# ISO_CAN_Module.net
KiCad netlist of a schematic drawn in EAGLE
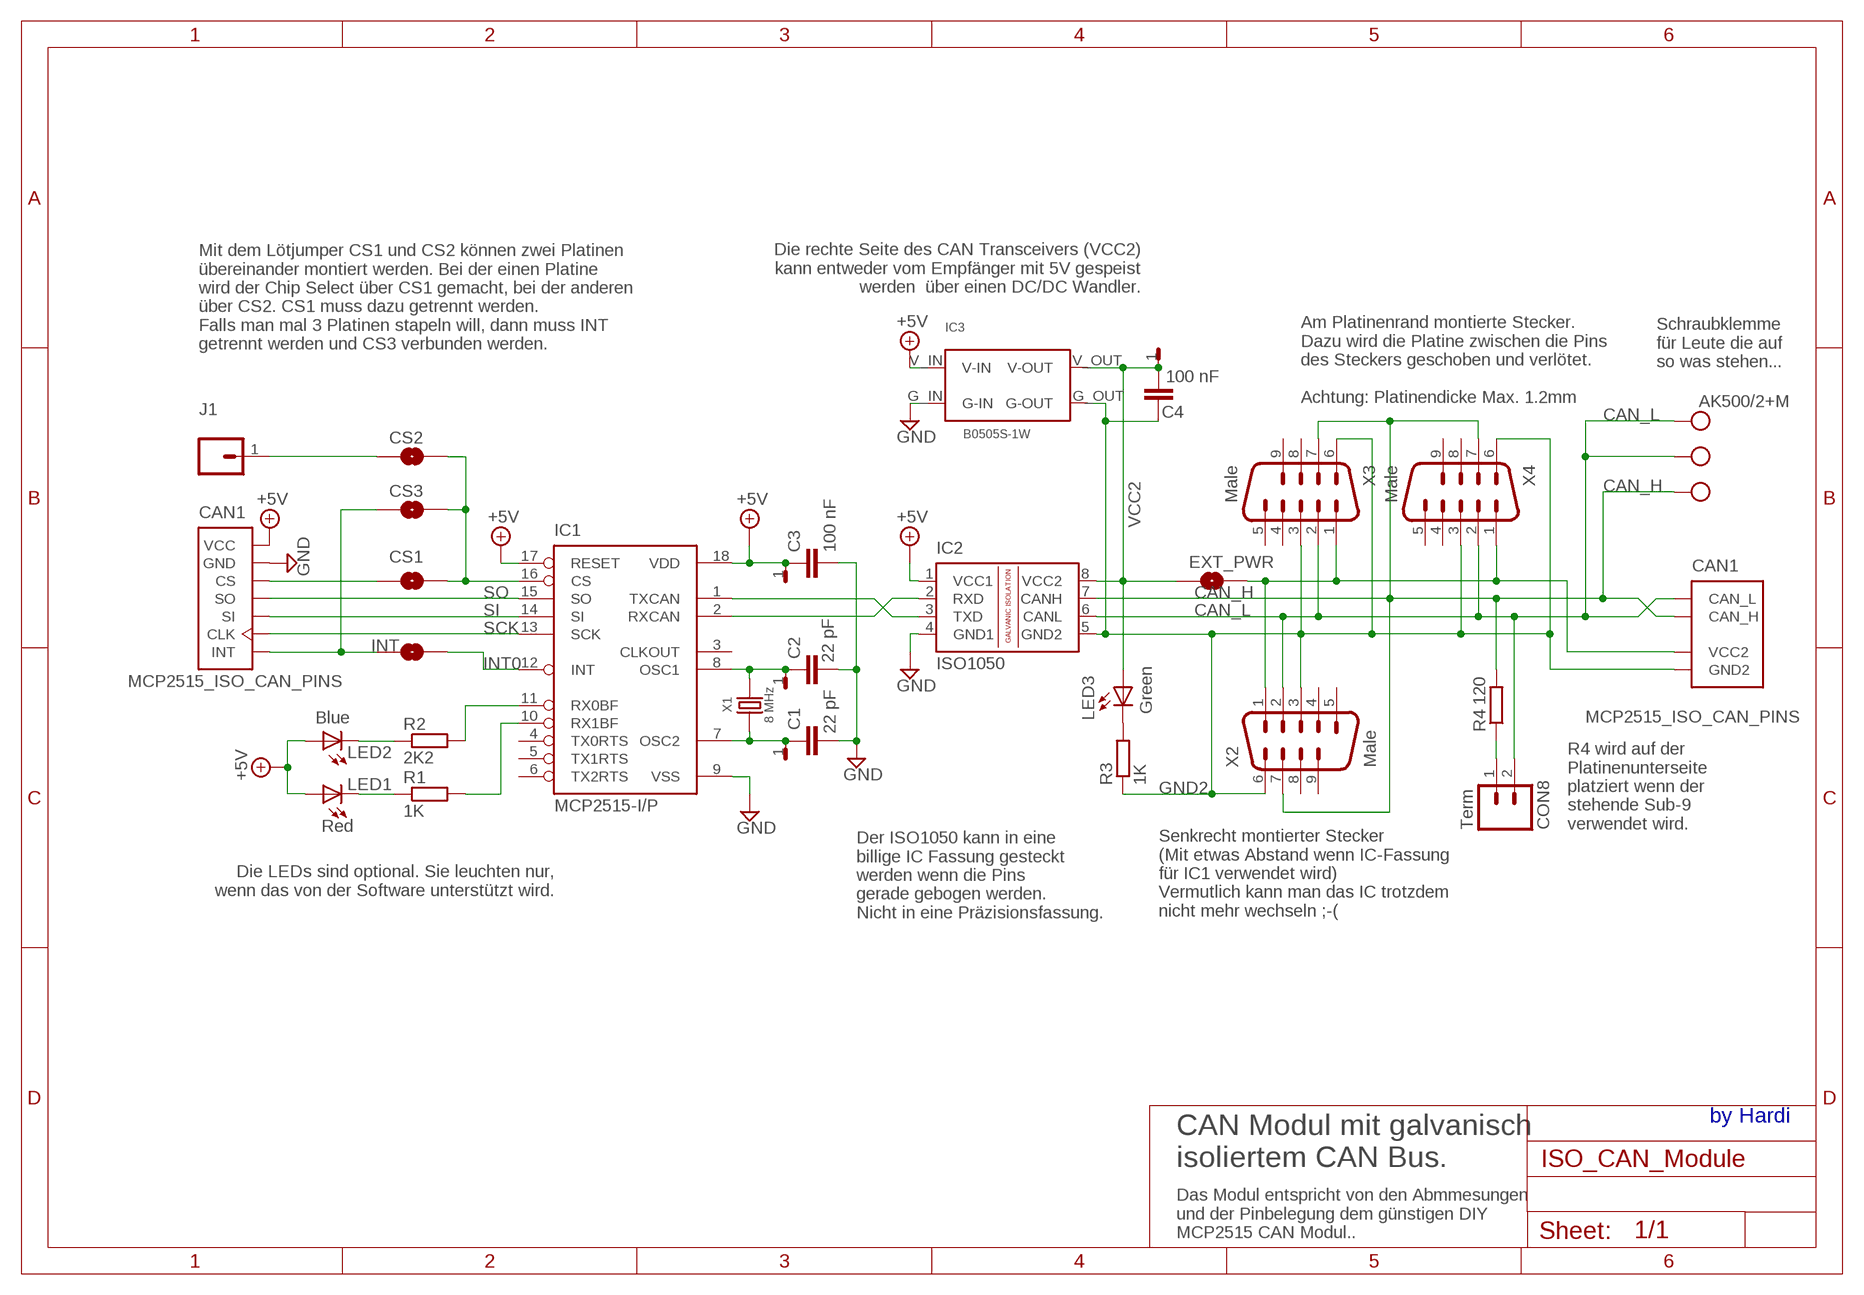
[diagram p0: schematic, sheet 1]

(export (version "E")
  (design (tool "Eeschema 10.0.6"))
  (components
    (comp (ref "C1")
      (value "22 pF")
      (footprint "eagle-import:C2.5-2")
      (libsource (lib "eagle-import") (part "C2.5/2"))
    )
    (comp (ref "C2")
      (value "22 pF")
      (footprint "eagle-import:C2.5-2")
      (libsource (lib "eagle-import") (part "C2.5/2"))
    )
    (comp (ref "C3")
      (value "100 nF")
      (footprint "eagle-import:C2.5-2")
      (libsource (lib "eagle-import") (part "C2.5/2"))
    )
    (comp (ref "C4")
      (value "100 nF")
      (footprint "eagle-import:C2.5-2")
      (libsource (lib "eagle-import") (part "C2.5/2"))
    )
    (comp (ref "CAN1")
      (value "MCP2515_ISO_CAN_PINS")
      (footprint "eagle-import:MCP2515_ISO_CAN")
      (libsource (lib "eagle-import") (part "MCP2515_ISO_CAN_PINS"))
    )
    (comp (ref "CON8")
      (value "Term")
      (footprint "eagle-import:1X02")
      (libsource (lib "eagle-import") (part "M02PTH"))
    )
    (comp (ref "CS1")
      (value "SOLDERJUMPERTRACE")
      (footprint "eagle-import:SJ_2S-TRACE")
      (libsource (lib "eagle-import") (part "SOLDERJUMPERTRACE"))
    )
    (comp (ref "CS2")
      (value "SOLDERJUMPERNO")
      (footprint "eagle-import:SJ_2S-NO")
      (libsource (lib "eagle-import") (part "SOLDERJUMPERNO"))
    )
    (comp (ref "CS3")
      (value "SOLDERJUMPERNO")
      (footprint "eagle-import:SJ_2S-NO")
      (libsource (lib "eagle-import") (part "SOLDERJUMPERNO"))
    )
    (comp (ref "EXT_PWR")
      (value "SOLDERJUMPERNO")
      (footprint "eagle-import:SJ_2S-NO")
      (libsource (lib "eagle-import") (part "SOLDERJUMPERNO"))
    )
    (comp (ref "IC1")
      (value "MCP2515-I/P")
      (footprint "eagle-import:DIL18")
      (libsource (lib "eagle-import") (part "MCP2515-I/P"))
    )
    (comp (ref "IC2")
      (value "ISO1050")
      (footprint "eagle-import:DIL08")
      (libsource (lib "eagle-import") (part "ISO1050"))
    )
    (comp (ref "IC3")
      (value "B0505S-1W")
      (footprint "eagle-import:DCDC-TEA_NME")
      (libsource (lib "eagle-import") (part "DCDC"))
    )
    (comp (ref "INT")
      (value "SOLDERJUMPERTRACE")
      (footprint "eagle-import:SJ_2S-TRACE")
      (libsource (lib "eagle-import") (part "SOLDERJUMPERTRACE"))
    )
    (comp (ref "J1")
      (value "M01")
      (footprint "eagle-import:1X01")
      (libsource (lib "eagle-import") (part "M01"))
    )
    (comp (ref "J2")
      (value "M01S")
      (footprint "eagle-import:1X01S")
      (libsource (lib "eagle-import") (part "M01S"))
    )
    (comp (ref "J3")
      (value "M01S")
      (footprint "eagle-import:1X01S")
      (libsource (lib "eagle-import") (part "M01S"))
    )
    (comp (ref "J4")
      (value "M01S")
      (footprint "eagle-import:1X01S")
      (libsource (lib "eagle-import") (part "M01S"))
    )
    (comp (ref "J5")
      (value "M01S")
      (footprint "eagle-import:1X01S")
      (libsource (lib "eagle-import") (part "M01S"))
    )
    (comp (ref "LED1")
      (value "Red")
      (footprint "eagle-import:CHIPLED_0805")
      (libsource (lib "eagle-import") (part "LEDCHIPLED_0805"))
    )
    (comp (ref "LED2")
      (value "Blue")
      (footprint "eagle-import:CHIPLED_0805")
      (libsource (lib "eagle-import") (part "LEDCHIPLED_0805"))
    )
    (comp (ref "LED3")
      (value "Green")
      (footprint "eagle-import:CHIPLED_0805")
      (libsource (lib "eagle-import") (part "LEDCHIPLED_0805"))
    )
    (comp (ref "R1")
      (value "1K")
      (footprint "eagle-import:M0805")
      (libsource (lib "eagle-import") (part "R-EU_M0805"))
    )
    (comp (ref "R2")
      (value "2K2")
      (footprint "eagle-import:M0805")
      (libsource (lib "eagle-import") (part "R-EU_M0805"))
    )
    (comp (ref "R3")
      (value "1K")
      (footprint "eagle-import:M0805")
      (libsource (lib "eagle-import") (part "R-EU_M0805"))
    )
    (comp (ref "R4")
      (value "120")
      (footprint "eagle-import:0204_7")
      (libsource (lib "eagle-import") (part "R-EU_0204/7"))
    )
    (comp (ref "X1")
      (value "8 MHz")
      (footprint "eagle-import:HC49U-V")
      (libsource (lib "eagle-import") (part "CRYSTAL-HC49U-V"))
    )
    (comp (ref "X2")
      (value "Male")
      (footprint "eagle-import:M09VB")
      (libsource (lib "eagle-import") (part "M09VB"))
    )
    (comp (ref "X3")
      (value "Male")
      (footprint "eagle-import:M09D")
      (libsource (lib "eagle-import") (part "M09D"))
    )
    (comp (ref "X4")
      (value "Male")
      (footprint "eagle-import:M09D")
      (libsource (lib "eagle-import") (part "M09D"))
    )
    (comp (ref "X5")
      (value "AK500/2+M")
      (footprint "eagle-import:AK500_2+M")
      (libsource (lib "eagle-import") (part "AK500/2+M"))
    )
  )
  (nets
    (net (code "1") (name "+5V") (class "Default")
      (node (ref "C3") (pin "1") (pinfunction "1_1") (pintype "passive"))
      (node (ref "CAN1") (pin "1") (pinfunction "VCC_1") (pintype "power_in"))
      (node (ref "IC1") (pin "17") (pinfunction "RESET_17") (pintype "input"))
      (node (ref "IC1") (pin "18") (pinfunction "VDD_18") (pintype "power_in"))
      (node (ref "IC2") (pin "1") (pinfunction "VCC1_1") (pintype "input"))
      (node (ref "IC3") (pin "V_IN") (pinfunction "V-IN_V_IN") (pintype "bidirectional"))
      (node (ref "J4") (pin "1") (pinfunction "1_1") (pintype "passive"))
      (node (ref "LED1") (pin "A") (pinfunction "A_A") (pintype "passive"))
      (node (ref "LED2") (pin "A") (pinfunction "A_A") (pintype "passive"))
    )
    (net (code "2") (name "/CAN_H") (class "Default")
      (node (ref "CAN1") (pin "9") (pinfunction "CAN_H_9") (pintype "bidirectional"))
      (node (ref "IC2") (pin "7") (pinfunction "CANH_7") (pintype "input"))
      (node (ref "R4") (pin "2") (pinfunction "2_2") (pintype "passive"))
      (node (ref "X2") (pin "7") (pinfunction "7_7") (pintype "passive"))
      (node (ref "X3") (pin "7") (pinfunction "7_7") (pintype "passive"))
      (node (ref "X4") (pin "7") (pinfunction "7_7") (pintype "passive"))
      (node (ref "X5") (pin "2") (pinfunction "KL_2") (pintype "passive"))
    )
    (net (code "3") (name "/CAN_L") (class "Default")
      (node (ref "CAN1") (pin "8") (pinfunction "CAN_L_8") (pintype "bidirectional"))
      (node (ref "CON8") (pin "2") (pinfunction "2_2") (pintype "passive"))
      (node (ref "IC2") (pin "6") (pinfunction "CANL_6") (pintype "input"))
      (node (ref "X2") (pin "2") (pinfunction "2_2") (pintype "passive"))
      (node (ref "X3") (pin "2") (pinfunction "2_2") (pintype "passive"))
      (node (ref "X4") (pin "2") (pinfunction "2_2") (pintype "passive"))
      (node (ref "X5") (pin "1") (pinfunction "KL_1") (pintype "passive"))
      (node (ref "X5") (pin "M") (pinfunction "KL_M") (pintype "passive"))
    )
    (net (code "4") (name "/GND2") (class "Default")
      (node (ref "C4") (pin "1") (pinfunction "1_1") (pintype "passive"))
      (node (ref "CAN1") (pin "11") (pinfunction "GND2_11") (pintype "power_in"))
      (node (ref "IC2") (pin "5") (pinfunction "GND2_5") (pintype "input"))
      (node (ref "IC3") (pin "G_OUT") (pinfunction "G-OUT_G_OUT") (pintype "bidirectional"))
      (node (ref "R3") (pin "1") (pinfunction "1_1") (pintype "passive"))
      (node (ref "X2") (pin "3") (pinfunction "3_3") (pintype "passive"))
      (node (ref "X2") (pin "6") (pinfunction "6_6") (pintype "passive"))
      (node (ref "X3") (pin "3") (pinfunction "3_3") (pintype "passive"))
      (node (ref "X3") (pin "6") (pinfunction "6_6") (pintype "passive"))
      (node (ref "X4") (pin "3") (pinfunction "3_3") (pintype "passive"))
      (node (ref "X4") (pin "6") (pinfunction "6_6") (pintype "passive"))
    )
    (net (code "5") (name "/INT0") (class "Default")
      (node (ref "IC1") (pin "12") (pinfunction "INT_12") (pintype "output"))
      (node (ref "INT") (pin "2") (pinfunction "2_2") (pintype "passive"))
    )
    (net (code "6") (name "/SCK") (class "Default")
      (node (ref "CAN1") (pin "6") (pinfunction "CLK_6") (pintype "input"))
      (node (ref "IC1") (pin "13") (pinfunction "SCK_13") (pintype "input"))
    )
    (net (code "7") (name "/SI") (class "Default")
      (node (ref "CAN1") (pin "5") (pinfunction "SI_5") (pintype "input"))
      (node (ref "IC1") (pin "14") (pinfunction "SI_14") (pintype "input"))
    )
    (net (code "8") (name "/SO") (class "Default")
      (node (ref "CAN1") (pin "4") (pinfunction "SO_4") (pintype "output"))
      (node (ref "IC1") (pin "15") (pinfunction "SO_15") (pintype "output"))
    )
    (net (code "9") (name "/VCC2") (class "Default")
      (node (ref "C4") (pin "2") (pinfunction "2_2") (pintype "passive"))
      (node (ref "EXT_PWR") (pin "1") (pinfunction "1_1") (pintype "passive"))
      (node (ref "IC2") (pin "8") (pinfunction "VCC2_8") (pintype "input"))
      (node (ref "IC3") (pin "V_OUT") (pinfunction "V-OUT_V_OUT") (pintype "bidirectional"))
      (node (ref "J5") (pin "1") (pinfunction "1_1") (pintype "passive"))
      (node (ref "LED3") (pin "A") (pinfunction "A_A") (pintype "passive"))
    )
    (net (code "10") (name "GND") (class "Default")
      (node (ref "C1") (pin "2") (pinfunction "2_2") (pintype "passive"))
      (node (ref "C2") (pin "2") (pinfunction "2_2") (pintype "passive"))
      (node (ref "C3") (pin "2") (pinfunction "2_2") (pintype "passive"))
      (node (ref "CAN1") (pin "2") (pinfunction "GND_2") (pintype "power_in"))
      (node (ref "IC1") (pin "9") (pinfunction "VSS_9") (pintype "power_in"))
      (node (ref "IC2") (pin "4") (pinfunction "GND1_4") (pintype "input"))
      (node (ref "IC3") (pin "G_IN") (pinfunction "G-IN_G_IN") (pintype "bidirectional"))
    )
    (net (code "11") (name "Net-(CAN1A-CS)") (class "Default")
      (node (ref "CAN1") (pin "3") (pinfunction "CS_3") (pintype "input"))
      (node (ref "CS1") (pin "1") (pinfunction "1_1") (pintype "passive"))
    )
    (net (code "12") (name "Net-(CAN1A-INT)") (class "Default")
      (node (ref "CAN1") (pin "7") (pinfunction "INT_7") (pintype "open_collector"))
      (node (ref "CS3") (pin "1") (pinfunction "1_1") (pintype "passive"))
      (node (ref "INT") (pin "1") (pinfunction "1_1") (pintype "passive"))
    )
    (net (code "13") (name "Net-(CAN1B-VCC2)") (class "Default")
      (node (ref "CAN1") (pin "10") (pinfunction "VCC2_10") (pintype "power_in"))
      (node (ref "EXT_PWR") (pin "2") (pinfunction "2_2") (pintype "passive"))
      (node (ref "X2") (pin "1") (pinfunction "1_1") (pintype "passive"))
      (node (ref "X3") (pin "1") (pinfunction "1_1") (pintype "passive"))
      (node (ref "X4") (pin "1") (pinfunction "1_1") (pintype "passive"))
    )
    (net (code "14") (name "Net-(CON8-Pad1)") (class "Default")
      (node (ref "CON8") (pin "1") (pinfunction "1_1") (pintype "passive"))
      (node (ref "R4") (pin "1") (pinfunction "1_1") (pintype "passive"))
    )
    (net (code "15") (name "Net-(CS2-Pad1)") (class "Default")
      (node (ref "CS2") (pin "1") (pinfunction "1_1") (pintype "passive"))
      (node (ref "J1") (pin "1") (pinfunction "1_1") (pintype "passive"))
    )
    (net (code "16") (name "Net-(IC1-CS)") (class "Default")
      (node (ref "CS1") (pin "2") (pinfunction "2_2") (pintype "passive"))
      (node (ref "CS2") (pin "2") (pinfunction "2_2") (pintype "passive"))
      (node (ref "CS3") (pin "2") (pinfunction "2_2") (pintype "passive"))
      (node (ref "IC1") (pin "16") (pinfunction "CS_16") (pintype "input"))
    )
    (net (code "17") (name "Net-(IC1-OSC1)") (class "Default")
      (node (ref "C2") (pin "1") (pinfunction "1_1") (pintype "passive"))
      (node (ref "IC1") (pin "8") (pinfunction "OSC1_8") (pintype "input"))
      (node (ref "J3") (pin "1") (pinfunction "1_1") (pintype "passive"))
      (node (ref "X1") (pin "2") (pinfunction "2_2") (pintype "passive"))
    )
    (net (code "18") (name "Net-(IC1-OSC2)") (class "Default")
      (node (ref "C1") (pin "1") (pinfunction "1_1") (pintype "passive"))
      (node (ref "IC1") (pin "7") (pinfunction "OSC2_7") (pintype "output"))
      (node (ref "J2") (pin "1") (pinfunction "1_1") (pintype "passive"))
      (node (ref "X1") (pin "1") (pinfunction "1_1") (pintype "passive"))
    )
    (net (code "19") (name "Net-(IC1-RX0BF)") (class "Default")
      (node (ref "IC1") (pin "11") (pinfunction "RX0BF_11") (pintype "output"))
      (node (ref "R2") (pin "2") (pinfunction "2_2") (pintype "passive"))
    )
    (net (code "20") (name "Net-(IC1-RX1BF)") (class "Default")
      (node (ref "IC1") (pin "10") (pinfunction "RX1BF_10") (pintype "output"))
      (node (ref "R1") (pin "2") (pinfunction "2_2") (pintype "passive"))
    )
    (net (code "21") (name "Net-(IC1-RXCAN)") (class "Default")
      (node (ref "IC1") (pin "2") (pinfunction "RXCAN_2") (pintype "input"))
      (node (ref "IC2") (pin "2") (pinfunction "RXD_2") (pintype "input"))
    )
    (net (code "22") (name "Net-(IC1-TXCAN)") (class "Default")
      (node (ref "IC1") (pin "1") (pinfunction "TXCAN_1") (pintype "output"))
      (node (ref "IC2") (pin "3") (pinfunction "TXD_3") (pintype "input"))
    )
    (net (code "23") (name "Net-(LED1-PadC)") (class "Default")
      (node (ref "LED1") (pin "C") (pinfunction "C_C") (pintype "passive"))
      (node (ref "R1") (pin "1") (pinfunction "1_1") (pintype "passive"))
    )
    (net (code "24") (name "Net-(LED2-PadC)") (class "Default")
      (node (ref "LED2") (pin "C") (pinfunction "C_C") (pintype "passive"))
      (node (ref "R2") (pin "1") (pinfunction "1_1") (pintype "passive"))
    )
    (net (code "25") (name "Net-(LED3-PadC)") (class "Default")
      (node (ref "LED3") (pin "C") (pinfunction "C_C") (pintype "passive"))
      (node (ref "R3") (pin "2") (pinfunction "2_2") (pintype "passive"))
    )
    (net (code "26") (name "unconnected-(IC1-CLKOUT-Pad3)") (class "Default")
      (node (ref "IC1") (pin "3") (pinfunction "CLKOUT_3") (pintype "output"))
    )
    (net (code "27") (name "unconnected-(IC1-TX0RTS-Pad4)") (class "Default")
      (node (ref "IC1") (pin "4") (pinfunction "TX0RTS_4") (pintype "input"))
    )
    (net (code "28") (name "unconnected-(IC1-TX1RTS-Pad5)") (class "Default")
      (node (ref "IC1") (pin "5") (pinfunction "TX1RTS_5") (pintype "input"))
    )
    (net (code "29") (name "unconnected-(IC1-TX2RTS-Pad6)") (class "Default")
      (node (ref "IC1") (pin "6") (pinfunction "TX2RTS_6") (pintype "input"))
    )
    (net (code "30") (name "unconnected-(X2-Pad4)") (class "Default")
      (node (ref "X2") (pin "4") (pinfunction "4_4") (pintype "passive"))
    )
    (net (code "31") (name "unconnected-(X2-Pad5)") (class "Default")
      (node (ref "X2") (pin "5") (pinfunction "5_5") (pintype "passive"))
    )
    (net (code "32") (name "unconnected-(X2-Pad8)") (class "Default")
      (node (ref "X2") (pin "8") (pinfunction "8_8") (pintype "passive"))
    )
    (net (code "33") (name "unconnected-(X2-Pad9)") (class "Default")
      (node (ref "X2") (pin "9") (pinfunction "9_9") (pintype "passive"))
    )
    (net (code "34") (name "unconnected-(X3-Pad4)") (class "Default")
      (node (ref "X3") (pin "4") (pinfunction "4_4") (pintype "passive"))
    )
    (net (code "35") (name "unconnected-(X3-Pad5)") (class "Default")
      (node (ref "X3") (pin "5") (pinfunction "5_5") (pintype "passive"))
    )
    (net (code "36") (name "unconnected-(X3-Pad8)") (class "Default")
      (node (ref "X3") (pin "8") (pinfunction "8_8") (pintype "passive"))
    )
    (net (code "37") (name "unconnected-(X3-Pad9)") (class "Default")
      (node (ref "X3") (pin "9") (pinfunction "9_9") (pintype "passive"))
    )
    (net (code "38") (name "unconnected-(X4-Pad4)") (class "Default")
      (node (ref "X4") (pin "4") (pinfunction "4_4") (pintype "passive"))
    )
    (net (code "39") (name "unconnected-(X4-Pad5)") (class "Default")
      (node (ref "X4") (pin "5") (pinfunction "5_5") (pintype "passive"))
    )
    (net (code "40") (name "unconnected-(X4-Pad8)") (class "Default")
      (node (ref "X4") (pin "8") (pinfunction "8_8") (pintype "passive"))
    )
    (net (code "41") (name "unconnected-(X4-Pad9)") (class "Default")
      (node (ref "X4") (pin "9") (pinfunction "9_9") (pintype "passive"))
    )
  )
)
